# 2.net
KiCad netlist of a schematic drawn in Altium Designer
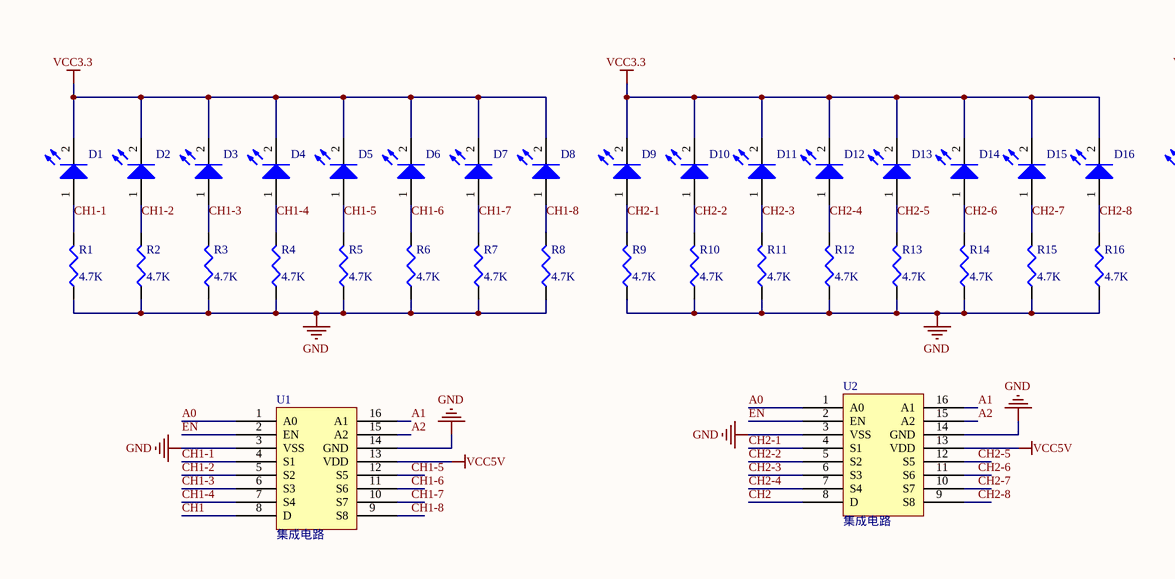
[diagram p0: 数粒机接收板2通道.SchDoc, left]
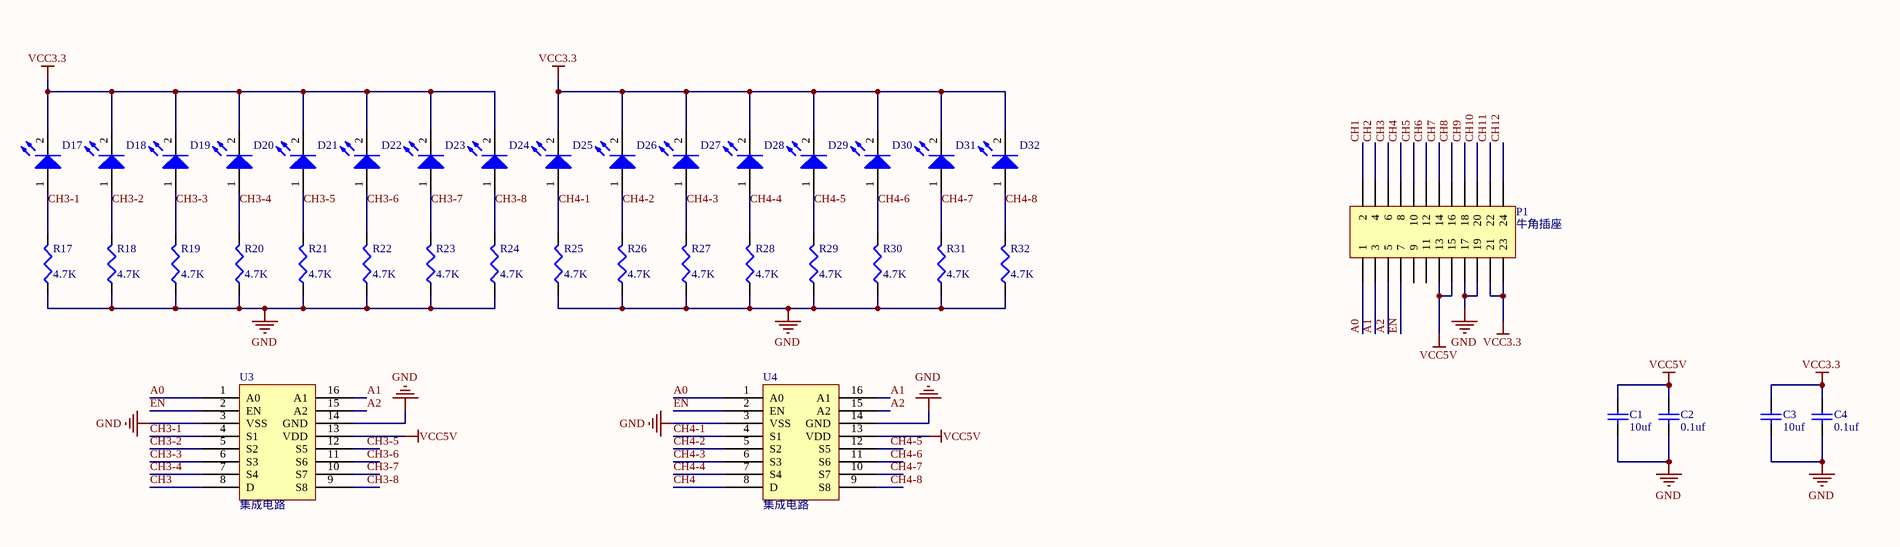
[diagram p1: 数粒机接收板2通道.SchDoc, right]

(export (version "E")
  (design (tool "Eeschema 10.0.6"))
  (components
    (comp (ref "C1")
      (value "10uf")
      (footprint "0805c")
      (description "Capacitor 10uf")
      (fields (field (name "Comment") "贴片电容 10uf") (field (name "PUBLISHER") "Altium Limited"))
      (libsource (lib "Miscellaneous Devices") (part "Cap"))
    )
    (comp (ref "C2")
      (value "0.1uf")
      (footprint "0805c")
      (description "Capacitor 0.1uf")
      (fields (field (name "Comment") "贴片电容 0.1uf") (field (name "PUBLISHER") "Altium Limited"))
      (libsource (lib "Miscellaneous Devices") (part "Cap"))
    )
    (comp (ref "C3")
      (value "10uf")
      (footprint "0805c")
      (description "Capacitor 10uf")
      (fields (field (name "Comment") "贴片电容 10uf") (field (name "PUBLISHER") "Altium Limited"))
      (libsource (lib "Miscellaneous Devices") (part "Cap"))
    )
    (comp (ref "C4")
      (value "0.1uf")
      (footprint "0805c")
      (description "Capacitor 0.1uf")
      (fields (field (name "Comment") "贴片电容 0.1uf") (field (name "PUBLISHER") "Altium Limited"))
      (libsource (lib "Miscellaneous Devices") (part "Cap"))
    )
    (comp (ref "D1")
      (value "红外接收珠子")
      (footprint "jieshou1206")
      (description "PD15-21B/TR8")
      (fields (field (name "PUBLISHER") "Altium Limited"))
      (libsource (lib "Miscellaneous Devices") (part "PD15-21B/TR8"))
    )
    (comp (ref "D2")
      (value "红外接收珠子")
      (footprint "jieshou1206")
      (description "PD15-21B/TR8")
      (fields (field (name "PUBLISHER") "Altium Limited"))
      (libsource (lib "Miscellaneous Devices") (part "PD15-21B/TR8"))
    )
    (comp (ref "D3")
      (value "红外接收珠子")
      (footprint "jieshou1206")
      (description "PD15-21B/TR8")
      (fields (field (name "PUBLISHER") "Altium Limited"))
      (libsource (lib "Miscellaneous Devices") (part "PD15-21B/TR8"))
    )
    (comp (ref "D4")
      (value "红外接收珠子")
      (footprint "jieshou1206")
      (description "PD15-21B/TR8")
      (fields (field (name "PUBLISHER") "Altium Limited"))
      (libsource (lib "Miscellaneous Devices") (part "PD15-21B/TR8"))
    )
    (comp (ref "D5")
      (value "红外接收珠子")
      (footprint "jieshou1206")
      (description "PD15-21B/TR8")
      (fields (field (name "PUBLISHER") "Altium Limited"))
      (libsource (lib "Miscellaneous Devices") (part "PD15-21B/TR8"))
    )
    (comp (ref "D6")
      (value "红外接收珠子")
      (footprint "jieshou1206")
      (description "PD15-21B/TR8")
      (fields (field (name "PUBLISHER") "Altium Limited"))
      (libsource (lib "Miscellaneous Devices") (part "PD15-21B/TR8"))
    )
    (comp (ref "D7")
      (value "红外接收珠子")
      (footprint "jieshou1206")
      (description "PD15-21B/TR8")
      (fields (field (name "PUBLISHER") "Altium Limited"))
      (libsource (lib "Miscellaneous Devices") (part "PD15-21B/TR8"))
    )
    (comp (ref "D8")
      (value "红外接收珠子")
      (footprint "jieshou1206")
      (description "PD15-21B/TR8")
      (fields (field (name "PUBLISHER") "Altium Limited"))
      (libsource (lib "Miscellaneous Devices") (part "PD15-21B/TR8"))
    )
    (comp (ref "D9")
      (value "红外接收珠子")
      (footprint "jieshou1206")
      (description "PD15-21B/TR8")
      (fields (field (name "PUBLISHER") "Altium Limited"))
      (libsource (lib "Miscellaneous Devices") (part "PD15-21B/TR8"))
    )
    (comp (ref "D10")
      (value "红外接收珠子")
      (footprint "jieshou1206")
      (description "PD15-21B/TR8")
      (fields (field (name "PUBLISHER") "Altium Limited"))
      (libsource (lib "Miscellaneous Devices") (part "PD15-21B/TR8"))
    )
    (comp (ref "D11")
      (value "红外接收珠子")
      (footprint "jieshou1206")
      (description "PD15-21B/TR8")
      (fields (field (name "PUBLISHER") "Altium Limited"))
      (libsource (lib "Miscellaneous Devices") (part "PD15-21B/TR8"))
    )
    (comp (ref "D12")
      (value "红外接收珠子")
      (footprint "jieshou1206")
      (description "PD15-21B/TR8")
      (fields (field (name "PUBLISHER") "Altium Limited"))
      (libsource (lib "Miscellaneous Devices") (part "PD15-21B/TR8"))
    )
    (comp (ref "D13")
      (value "红外接收珠子")
      (footprint "jieshou1206")
      (description "PD15-21B/TR8")
      (fields (field (name "PUBLISHER") "Altium Limited"))
      (libsource (lib "Miscellaneous Devices") (part "PD15-21B/TR8"))
    )
    (comp (ref "D14")
      (value "红外接收珠子")
      (footprint "jieshou1206")
      (description "PD15-21B/TR8")
      (fields (field (name "PUBLISHER") "Altium Limited"))
      (libsource (lib "Miscellaneous Devices") (part "PD15-21B/TR8"))
    )
    (comp (ref "D15")
      (value "红外接收珠子")
      (footprint "jieshou1206")
      (description "PD15-21B/TR8")
      (fields (field (name "PUBLISHER") "Altium Limited"))
      (libsource (lib "Miscellaneous Devices") (part "PD15-21B/TR8"))
    )
    (comp (ref "D16")
      (value "红外接收珠子")
      (footprint "jieshou1206")
      (description "PD15-21B/TR8")
      (fields (field (name "PUBLISHER") "Altium Limited"))
      (libsource (lib "Miscellaneous Devices") (part "PD15-21B/TR8"))
    )
    (comp (ref "D17")
      (value "红外接收珠子")
      (footprint "jieshou1206")
      (description "PD15-21B/TR8")
      (fields (field (name "PUBLISHER") "Altium Limited"))
      (libsource (lib "Miscellaneous Devices") (part "PD15-21B/TR8"))
    )
    (comp (ref "D18")
      (value "红外接收珠子")
      (footprint "jieshou1206")
      (description "PD15-21B/TR8")
      (fields (field (name "PUBLISHER") "Altium Limited"))
      (libsource (lib "Miscellaneous Devices") (part "PD15-21B/TR8"))
    )
    (comp (ref "D19")
      (value "红外接收珠子")
      (footprint "jieshou1206")
      (description "PD15-21B/TR8")
      (fields (field (name "PUBLISHER") "Altium Limited"))
      (libsource (lib "Miscellaneous Devices") (part "PD15-21B/TR8"))
    )
    (comp (ref "D20")
      (value "红外接收珠子")
      (footprint "jieshou1206")
      (description "PD15-21B/TR8")
      (fields (field (name "PUBLISHER") "Altium Limited"))
      (libsource (lib "Miscellaneous Devices") (part "PD15-21B/TR8"))
    )
    (comp (ref "D21")
      (value "红外接收珠子")
      (footprint "jieshou1206")
      (description "PD15-21B/TR8")
      (fields (field (name "PUBLISHER") "Altium Limited"))
      (libsource (lib "Miscellaneous Devices") (part "PD15-21B/TR8"))
    )
    (comp (ref "D22")
      (value "红外接收珠子")
      (footprint "jieshou1206")
      (description "PD15-21B/TR8")
      (fields (field (name "PUBLISHER") "Altium Limited"))
      (libsource (lib "Miscellaneous Devices") (part "PD15-21B/TR8"))
    )
    (comp (ref "D23")
      (value "红外接收珠子")
      (footprint "jieshou1206")
      (description "PD15-21B/TR8")
      (fields (field (name "PUBLISHER") "Altium Limited"))
      (libsource (lib "Miscellaneous Devices") (part "PD15-21B/TR8"))
    )
    (comp (ref "D24")
      (value "红外接收珠子")
      (footprint "jieshou1206")
      (description "PD15-21B/TR8")
      (fields (field (name "PUBLISHER") "Altium Limited"))
      (libsource (lib "Miscellaneous Devices") (part "PD15-21B/TR8"))
    )
    (comp (ref "D25")
      (value "红外接收珠子")
      (footprint "jieshou1206")
      (description "PD15-21B/TR8")
      (fields (field (name "PUBLISHER") "Altium Limited"))
      (libsource (lib "Miscellaneous Devices") (part "PD15-21B/TR8"))
    )
    (comp (ref "D26")
      (value "红外接收珠子")
      (footprint "jieshou1206")
      (description "PD15-21B/TR8")
      (fields (field (name "PUBLISHER") "Altium Limited"))
      (libsource (lib "Miscellaneous Devices") (part "PD15-21B/TR8"))
    )
    (comp (ref "D27")
      (value "红外接收珠子")
      (footprint "jieshou1206")
      (description "PD15-21B/TR8")
      (fields (field (name "PUBLISHER") "Altium Limited"))
      (libsource (lib "Miscellaneous Devices") (part "PD15-21B/TR8"))
    )
    (comp (ref "D28")
      (value "红外接收珠子")
      (footprint "jieshou1206")
      (description "PD15-21B/TR8")
      (fields (field (name "PUBLISHER") "Altium Limited"))
      (libsource (lib "Miscellaneous Devices") (part "PD15-21B/TR8"))
    )
    (comp (ref "D29")
      (value "红外接收珠子")
      (footprint "jieshou1206")
      (description "PD15-21B/TR8")
      (fields (field (name "PUBLISHER") "Altium Limited"))
      (libsource (lib "Miscellaneous Devices") (part "PD15-21B/TR8"))
    )
    (comp (ref "D30")
      (value "红外接收珠子")
      (footprint "jieshou1206")
      (description "PD15-21B/TR8")
      (fields (field (name "PUBLISHER") "Altium Limited"))
      (libsource (lib "Miscellaneous Devices") (part "PD15-21B/TR8"))
    )
    (comp (ref "D31")
      (value "红外接收珠子")
      (footprint "jieshou1206")
      (description "PD15-21B/TR8")
      (fields (field (name "PUBLISHER") "Altium Limited"))
      (libsource (lib "Miscellaneous Devices") (part "PD15-21B/TR8"))
    )
    (comp (ref "D32")
      (value "红外接收珠子")
      (footprint "jieshou1206")
      (description "PD15-21B/TR8")
      (fields (field (name "PUBLISHER") "Altium Limited"))
      (libsource (lib "Miscellaneous Devices") (part "PD15-21B/TR8"))
    )
    (comp (ref "P1")
      (value "牛角插座")
      (footprint "HDR2X12")
      (description "Header, 12-Pin, Dual row")
      (fields (field (name "PUBLISHER") "Altium Limited"))
      (libsource (lib "Miscellaneous Connectors") (part "Header 12X2"))
    )
    (comp (ref "R1")
      (value "4.7K")
      (footprint "0805r")
      (description "电阻")
      (fields (field (name "Comment") "贴片电阻") (field (name "PUBLISHER") "Altium Limited"))
      (libsource (lib "Miscellaneous Devices") (part "Res3"))
    )
    (comp (ref "R2")
      (value "4.7K")
      (footprint "0805r")
      (description "电阻")
      (fields (field (name "Comment") "贴片电阻") (field (name "PUBLISHER") "Altium Limited"))
      (libsource (lib "Miscellaneous Devices") (part "Res3"))
    )
    (comp (ref "R3")
      (value "4.7K")
      (footprint "0805r")
      (description "电阻")
      (fields (field (name "Comment") "贴片电阻") (field (name "PUBLISHER") "Altium Limited"))
      (libsource (lib "Miscellaneous Devices") (part "Res3"))
    )
    (comp (ref "R4")
      (value "4.7K")
      (footprint "0805r")
      (description "电阻")
      (fields (field (name "Comment") "贴片电阻") (field (name "PUBLISHER") "Altium Limited"))
      (libsource (lib "Miscellaneous Devices") (part "Res3"))
    )
    (comp (ref "R5")
      (value "4.7K")
      (footprint "0805r")
      (description "电阻")
      (fields (field (name "Comment") "贴片电阻") (field (name "PUBLISHER") "Altium Limited"))
      (libsource (lib "Miscellaneous Devices") (part "Res3"))
    )
    (comp (ref "R6")
      (value "4.7K")
      (footprint "0805r")
      (description "电阻")
      (fields (field (name "Comment") "贴片电阻") (field (name "PUBLISHER") "Altium Limited"))
      (libsource (lib "Miscellaneous Devices") (part "Res3"))
    )
    (comp (ref "R7")
      (value "4.7K")
      (footprint "0805r")
      (description "电阻")
      (fields (field (name "Comment") "贴片电阻") (field (name "PUBLISHER") "Altium Limited"))
      (libsource (lib "Miscellaneous Devices") (part "Res3"))
    )
    (comp (ref "R8")
      (value "4.7K")
      (footprint "0805r")
      (description "电阻")
      (fields (field (name "Comment") "贴片电阻") (field (name "PUBLISHER") "Altium Limited"))
      (libsource (lib "Miscellaneous Devices") (part "Res3"))
    )
    (comp (ref "R9")
      (value "4.7K")
      (footprint "0805r")
      (description "电阻")
      (fields (field (name "Comment") "贴片电阻") (field (name "PUBLISHER") "Altium Limited"))
      (libsource (lib "Miscellaneous Devices") (part "Res3"))
    )
    (comp (ref "R10")
      (value "4.7K")
      (footprint "0805r")
      (description "电阻")
      (fields (field (name "Comment") "贴片电阻") (field (name "PUBLISHER") "Altium Limited"))
      (libsource (lib "Miscellaneous Devices") (part "Res3"))
    )
    (comp (ref "R11")
      (value "4.7K")
      (footprint "0805r")
      (description "电阻")
      (fields (field (name "Comment") "贴片电阻") (field (name "PUBLISHER") "Altium Limited"))
      (libsource (lib "Miscellaneous Devices") (part "Res3"))
    )
    (comp (ref "R12")
      (value "4.7K")
      (footprint "0805r")
      (description "电阻")
      (fields (field (name "Comment") "贴片电阻") (field (name "PUBLISHER") "Altium Limited"))
      (libsource (lib "Miscellaneous Devices") (part "Res3"))
    )
    (comp (ref "R13")
      (value "4.7K")
      (footprint "0805r")
      (description "电阻")
      (fields (field (name "Comment") "贴片电阻") (field (name "PUBLISHER") "Altium Limited"))
      (libsource (lib "Miscellaneous Devices") (part "Res3"))
    )
    (comp (ref "R14")
      (value "4.7K")
      (footprint "0805r")
      (description "电阻")
      (fields (field (name "Comment") "贴片电阻") (field (name "PUBLISHER") "Altium Limited"))
      (libsource (lib "Miscellaneous Devices") (part "Res3"))
    )
    (comp (ref "R15")
      (value "4.7K")
      (footprint "0805r")
      (description "电阻")
      (fields (field (name "Comment") "贴片电阻") (field (name "PUBLISHER") "Altium Limited"))
      (libsource (lib "Miscellaneous Devices") (part "Res3"))
    )
    (comp (ref "R16")
      (value "4.7K")
      (footprint "0805r")
      (description "电阻")
      (fields (field (name "Comment") "贴片电阻") (field (name "PUBLISHER") "Altium Limited"))
      (libsource (lib "Miscellaneous Devices") (part "Res3"))
    )
    (comp (ref "R17")
      (value "4.7K")
      (footprint "0805r")
      (description "电阻")
      (fields (field (name "Comment") "贴片电阻") (field (name "PUBLISHER") "Altium Limited"))
      (libsource (lib "Miscellaneous Devices") (part "Res3"))
    )
    (comp (ref "R18")
      (value "4.7K")
      (footprint "0805r")
      (description "电阻")
      (fields (field (name "Comment") "贴片电阻") (field (name "PUBLISHER") "Altium Limited"))
      (libsource (lib "Miscellaneous Devices") (part "Res3"))
    )
    (comp (ref "R19")
      (value "4.7K")
      (footprint "0805r")
      (description "电阻")
      (fields (field (name "Comment") "贴片电阻") (field (name "PUBLISHER") "Altium Limited"))
      (libsource (lib "Miscellaneous Devices") (part "Res3"))
    )
    (comp (ref "R20")
      (value "4.7K")
      (footprint "0805r")
      (description "电阻")
      (fields (field (name "Comment") "贴片电阻") (field (name "PUBLISHER") "Altium Limited"))
      (libsource (lib "Miscellaneous Devices") (part "Res3"))
    )
    (comp (ref "R21")
      (value "4.7K")
      (footprint "0805r")
      (description "电阻")
      (fields (field (name "Comment") "贴片电阻") (field (name "PUBLISHER") "Altium Limited"))
      (libsource (lib "Miscellaneous Devices") (part "Res3"))
    )
    (comp (ref "R22")
      (value "4.7K")
      (footprint "0805r")
      (description "电阻")
      (fields (field (name "Comment") "贴片电阻") (field (name "PUBLISHER") "Altium Limited"))
      (libsource (lib "Miscellaneous Devices") (part "Res3"))
    )
    (comp (ref "R23")
      (value "4.7K")
      (footprint "0805r")
      (description "电阻")
      (fields (field (name "Comment") "贴片电阻") (field (name "PUBLISHER") "Altium Limited"))
      (libsource (lib "Miscellaneous Devices") (part "Res3"))
    )
    (comp (ref "R24")
      (value "4.7K")
      (footprint "0805r")
      (description "电阻")
      (fields (field (name "Comment") "贴片电阻") (field (name "PUBLISHER") "Altium Limited"))
      (libsource (lib "Miscellaneous Devices") (part "Res3"))
    )
    (comp (ref "R25")
      (value "4.7K")
      (footprint "0805r")
      (description "电阻")
      (fields (field (name "Comment") "贴片电阻") (field (name "PUBLISHER") "Altium Limited"))
      (libsource (lib "Miscellaneous Devices") (part "Res3"))
    )
    (comp (ref "R26")
      (value "4.7K")
      (footprint "0805r")
      (description "电阻")
      (fields (field (name "Comment") "贴片电阻") (field (name "PUBLISHER") "Altium Limited"))
      (libsource (lib "Miscellaneous Devices") (part "Res3"))
    )
    (comp (ref "R27")
      (value "4.7K")
      (footprint "0805r")
      (description "电阻")
      (fields (field (name "Comment") "贴片电阻") (field (name "PUBLISHER") "Altium Limited"))
      (libsource (lib "Miscellaneous Devices") (part "Res3"))
    )
    (comp (ref "R28")
      (value "4.7K")
      (footprint "0805r")
      (description "电阻")
      (fields (field (name "Comment") "贴片电阻") (field (name "PUBLISHER") "Altium Limited"))
      (libsource (lib "Miscellaneous Devices") (part "Res3"))
    )
    (comp (ref "R29")
      (value "4.7K")
      (footprint "0805r")
      (description "电阻")
      (fields (field (name "Comment") "贴片电阻") (field (name "PUBLISHER") "Altium Limited"))
      (libsource (lib "Miscellaneous Devices") (part "Res3"))
    )
    (comp (ref "R30")
      (value "4.7K")
      (footprint "0805r")
      (description "电阻")
      (fields (field (name "Comment") "贴片电阻") (field (name "PUBLISHER") "Altium Limited"))
      (libsource (lib "Miscellaneous Devices") (part "Res3"))
    )
    (comp (ref "R31")
      (value "4.7K")
      (footprint "0805r")
      (description "电阻")
      (fields (field (name "Comment") "贴片电阻") (field (name "PUBLISHER") "Altium Limited"))
      (libsource (lib "Miscellaneous Devices") (part "Res3"))
    )
    (comp (ref "R32")
      (value "4.7K")
      (footprint "0805r")
      (description "电阻")
      (fields (field (name "Comment") "贴片电阻") (field (name "PUBLISHER") "Altium Limited"))
      (libsource (lib "Miscellaneous Devices") (part "Res3"))
    )
    (comp (ref "U1")
      (value "集成电路")
      (footprint "TSSOP16")
      (description "ADG708BRU-REEL")
      (libsource (lib "MYlib") (part "ADG708"))
    )
    (comp (ref "U2")
      (value "集成电路")
      (footprint "TSSOP16")
      (description "ADG708BRU-REEL")
      (libsource (lib "MYlib") (part "ADG708"))
    )
    (comp (ref "U3")
      (value "集成电路")
      (footprint "TSSOP16")
      (description "ADG708BRU-REEL")
      (libsource (lib "MYlib") (part "ADG708"))
    )
    (comp (ref "U4")
      (value "集成电路")
      (footprint "TSSOP16")
      (description "ADG708BRU-REEL")
      (libsource (lib "MYlib") (part "ADG708"))
    )
  )
  (nets
    (net (code "1") (name "/A0") (class "Default")
      (node (ref "P1") (pin "1") (pinfunction "1_1") (pintype "passive"))
      (node (ref "U1") (pin "1") (pinfunction "A0_1") (pintype "passive"))
      (node (ref "U2") (pin "1") (pinfunction "A0_1") (pintype "passive"))
      (node (ref "U3") (pin "1") (pinfunction "A0_1") (pintype "passive"))
      (node (ref "U4") (pin "1") (pinfunction "A0_1") (pintype "passive"))
    )
    (net (code "2") (name "/A1") (class "Default")
      (node (ref "P1") (pin "3") (pinfunction "3_3") (pintype "passive"))
      (node (ref "U1") (pin "16") (pinfunction "A1_16") (pintype "passive"))
      (node (ref "U2") (pin "16") (pinfunction "A1_16") (pintype "passive"))
      (node (ref "U3") (pin "16") (pinfunction "A1_16") (pintype "passive"))
      (node (ref "U4") (pin "16") (pinfunction "A1_16") (pintype "passive"))
    )
    (net (code "3") (name "/A2") (class "Default")
      (node (ref "P1") (pin "5") (pinfunction "5_5") (pintype "passive"))
      (node (ref "U1") (pin "15") (pinfunction "A2_15") (pintype "passive"))
      (node (ref "U2") (pin "15") (pinfunction "A2_15") (pintype "passive"))
      (node (ref "U3") (pin "15") (pinfunction "A2_15") (pintype "passive"))
      (node (ref "U4") (pin "15") (pinfunction "A2_15") (pintype "passive"))
    )
    (net (code "4") (name "/CH1") (class "Default")
      (node (ref "P1") (pin "2") (pinfunction "2_2") (pintype "passive"))
      (node (ref "U1") (pin "8") (pinfunction "D_8") (pintype "passive"))
    )
    (net (code "5") (name "/CH1-1") (class "Default")
      (node (ref "D1") (pin "1") (pinfunction "A_1") (pintype "passive"))
      (node (ref "R1") (pin "2") (pinfunction "2_2") (pintype "passive"))
      (node (ref "U1") (pin "4") (pinfunction "S1_4") (pintype "passive"))
    )
    (net (code "6") (name "/CH1-2") (class "Default")
      (node (ref "D2") (pin "1") (pinfunction "A_1") (pintype "passive"))
      (node (ref "R2") (pin "2") (pinfunction "2_2") (pintype "passive"))
      (node (ref "U1") (pin "5") (pinfunction "S2_5") (pintype "passive"))
    )
    (net (code "7") (name "/CH1-3") (class "Default")
      (node (ref "D3") (pin "1") (pinfunction "A_1") (pintype "passive"))
      (node (ref "R3") (pin "2") (pinfunction "2_2") (pintype "passive"))
      (node (ref "U1") (pin "6") (pinfunction "S3_6") (pintype "passive"))
    )
    (net (code "8") (name "/CH1-4") (class "Default")
      (node (ref "D4") (pin "1") (pinfunction "A_1") (pintype "passive"))
      (node (ref "R4") (pin "2") (pinfunction "2_2") (pintype "passive"))
      (node (ref "U1") (pin "7") (pinfunction "S4_7") (pintype "passive"))
    )
    (net (code "9") (name "/CH1-5") (class "Default")
      (node (ref "D5") (pin "1") (pinfunction "A_1") (pintype "passive"))
      (node (ref "R5") (pin "2") (pinfunction "2_2") (pintype "passive"))
      (node (ref "U1") (pin "12") (pinfunction "S5_12") (pintype "passive"))
    )
    (net (code "10") (name "/CH1-6") (class "Default")
      (node (ref "D6") (pin "1") (pinfunction "A_1") (pintype "passive"))
      (node (ref "R6") (pin "2") (pinfunction "2_2") (pintype "passive"))
      (node (ref "U1") (pin "11") (pinfunction "S6_11") (pintype "passive"))
    )
    (net (code "11") (name "/CH1-7") (class "Default")
      (node (ref "D7") (pin "1") (pinfunction "A_1") (pintype "passive"))
      (node (ref "R7") (pin "2") (pinfunction "2_2") (pintype "passive"))
      (node (ref "U1") (pin "10") (pinfunction "S7_10") (pintype "passive"))
    )
    (net (code "12") (name "/CH1-8") (class "Default")
      (node (ref "D8") (pin "1") (pinfunction "A_1") (pintype "passive"))
      (node (ref "R8") (pin "2") (pinfunction "2_2") (pintype "passive"))
      (node (ref "U1") (pin "9") (pinfunction "S8_9") (pintype "passive"))
    )
    (net (code "13") (name "/CH2") (class "Default")
      (node (ref "P1") (pin "4") (pinfunction "4_4") (pintype "passive"))
      (node (ref "U2") (pin "8") (pinfunction "D_8") (pintype "passive"))
    )
    (net (code "14") (name "/CH2-1") (class "Default")
      (node (ref "D9") (pin "1") (pinfunction "A_1") (pintype "passive"))
      (node (ref "R9") (pin "2") (pinfunction "2_2") (pintype "passive"))
      (node (ref "U2") (pin "4") (pinfunction "S1_4") (pintype "passive"))
    )
    (net (code "15") (name "/CH2-2") (class "Default")
      (node (ref "D10") (pin "1") (pinfunction "A_1") (pintype "passive"))
      (node (ref "R10") (pin "2") (pinfunction "2_2") (pintype "passive"))
      (node (ref "U2") (pin "5") (pinfunction "S2_5") (pintype "passive"))
    )
    (net (code "16") (name "/CH2-3") (class "Default")
      (node (ref "D11") (pin "1") (pinfunction "A_1") (pintype "passive"))
      (node (ref "R11") (pin "2") (pinfunction "2_2") (pintype "passive"))
      (node (ref "U2") (pin "6") (pinfunction "S3_6") (pintype "passive"))
    )
    (net (code "17") (name "/CH2-4") (class "Default")
      (node (ref "D12") (pin "1") (pinfunction "A_1") (pintype "passive"))
      (node (ref "R12") (pin "2") (pinfunction "2_2") (pintype "passive"))
      (node (ref "U2") (pin "7") (pinfunction "S4_7") (pintype "passive"))
    )
    (net (code "18") (name "/CH2-5") (class "Default")
      (node (ref "D13") (pin "1") (pinfunction "A_1") (pintype "passive"))
      (node (ref "R13") (pin "2") (pinfunction "2_2") (pintype "passive"))
      (node (ref "U2") (pin "12") (pinfunction "S5_12") (pintype "passive"))
    )
    (net (code "19") (name "/CH2-6") (class "Default")
      (node (ref "D14") (pin "1") (pinfunction "A_1") (pintype "passive"))
      (node (ref "R14") (pin "2") (pinfunction "2_2") (pintype "passive"))
      (node (ref "U2") (pin "11") (pinfunction "S6_11") (pintype "passive"))
    )
    (net (code "20") (name "/CH2-7") (class "Default")
      (node (ref "D15") (pin "1") (pinfunction "A_1") (pintype "passive"))
      (node (ref "R15") (pin "2") (pinfunction "2_2") (pintype "passive"))
      (node (ref "U2") (pin "10") (pinfunction "S7_10") (pintype "passive"))
    )
    (net (code "21") (name "/CH2-8") (class "Default")
      (node (ref "D16") (pin "1") (pinfunction "A_1") (pintype "passive"))
      (node (ref "R16") (pin "2") (pinfunction "2_2") (pintype "passive"))
      (node (ref "U2") (pin "9") (pinfunction "S8_9") (pintype "passive"))
    )
    (net (code "22") (name "/CH3") (class "Default")
      (node (ref "P1") (pin "6") (pinfunction "6_6") (pintype "passive"))
      (node (ref "U3") (pin "8") (pinfunction "D_8") (pintype "passive"))
    )
    (net (code "23") (name "/CH3-1") (class "Default")
      (node (ref "D17") (pin "1") (pinfunction "A_1") (pintype "passive"))
      (node (ref "R17") (pin "2") (pinfunction "2_2") (pintype "passive"))
      (node (ref "U3") (pin "4") (pinfunction "S1_4") (pintype "passive"))
    )
    (net (code "24") (name "/CH3-2") (class "Default")
      (node (ref "D18") (pin "1") (pinfunction "A_1") (pintype "passive"))
      (node (ref "R18") (pin "2") (pinfunction "2_2") (pintype "passive"))
      (node (ref "U3") (pin "5") (pinfunction "S2_5") (pintype "passive"))
    )
    (net (code "25") (name "/CH3-3") (class "Default")
      (node (ref "D19") (pin "1") (pinfunction "A_1") (pintype "passive"))
      (node (ref "R19") (pin "2") (pinfunction "2_2") (pintype "passive"))
      (node (ref "U3") (pin "6") (pinfunction "S3_6") (pintype "passive"))
    )
    (net (code "26") (name "/CH3-4") (class "Default")
      (node (ref "D20") (pin "1") (pinfunction "A_1") (pintype "passive"))
      (node (ref "R20") (pin "2") (pinfunction "2_2") (pintype "passive"))
      (node (ref "U3") (pin "7") (pinfunction "S4_7") (pintype "passive"))
    )
    (net (code "27") (name "/CH3-5") (class "Default")
      (node (ref "D21") (pin "1") (pinfunction "A_1") (pintype "passive"))
      (node (ref "R21") (pin "2") (pinfunction "2_2") (pintype "passive"))
      (node (ref "U3") (pin "12") (pinfunction "S5_12") (pintype "passive"))
    )
    (net (code "28") (name "/CH3-6") (class "Default")
      (node (ref "D22") (pin "1") (pinfunction "A_1") (pintype "passive"))
      (node (ref "R22") (pin "2") (pinfunction "2_2") (pintype "passive"))
      (node (ref "U3") (pin "11") (pinfunction "S6_11") (pintype "passive"))
    )
    (net (code "29") (name "/CH3-7") (class "Default")
      (node (ref "D23") (pin "1") (pinfunction "A_1") (pintype "passive"))
      (node (ref "R23") (pin "2") (pinfunction "2_2") (pintype "passive"))
      (node (ref "U3") (pin "10") (pinfunction "S7_10") (pintype "passive"))
    )
    (net (code "30") (name "/CH3-8") (class "Default")
      (node (ref "D24") (pin "1") (pinfunction "A_1") (pintype "passive"))
      (node (ref "R24") (pin "2") (pinfunction "2_2") (pintype "passive"))
      (node (ref "U3") (pin "9") (pinfunction "S8_9") (pintype "passive"))
    )
    (net (code "31") (name "/CH4") (class "Default")
      (node (ref "P1") (pin "8") (pinfunction "8_8") (pintype "passive"))
      (node (ref "U4") (pin "8") (pinfunction "D_8") (pintype "passive"))
    )
    (net (code "32") (name "/CH4-1") (class "Default")
      (node (ref "D25") (pin "1") (pinfunction "A_1") (pintype "passive"))
      (node (ref "R25") (pin "2") (pinfunction "2_2") (pintype "passive"))
      (node (ref "U4") (pin "4") (pinfunction "S1_4") (pintype "passive"))
    )
    (net (code "33") (name "/CH4-2") (class "Default")
      (node (ref "D26") (pin "1") (pinfunction "A_1") (pintype "passive"))
      (node (ref "R26") (pin "2") (pinfunction "2_2") (pintype "passive"))
      (node (ref "U4") (pin "5") (pinfunction "S2_5") (pintype "passive"))
    )
    (net (code "34") (name "/CH4-3") (class "Default")
      (node (ref "D27") (pin "1") (pinfunction "A_1") (pintype "passive"))
      (node (ref "R27") (pin "2") (pinfunction "2_2") (pintype "passive"))
      (node (ref "U4") (pin "6") (pinfunction "S3_6") (pintype "passive"))
    )
    (net (code "35") (name "/CH4-4") (class "Default")
      (node (ref "D28") (pin "1") (pinfunction "A_1") (pintype "passive"))
      (node (ref "R28") (pin "2") (pinfunction "2_2") (pintype "passive"))
      (node (ref "U4") (pin "7") (pinfunction "S4_7") (pintype "passive"))
    )
    (net (code "36") (name "/CH4-5") (class "Default")
      (node (ref "D29") (pin "1") (pinfunction "A_1") (pintype "passive"))
      (node (ref "R29") (pin "2") (pinfunction "2_2") (pintype "passive"))
      (node (ref "U4") (pin "12") (pinfunction "S5_12") (pintype "passive"))
    )
    (net (code "37") (name "/CH4-6") (class "Default")
      (node (ref "D30") (pin "1") (pinfunction "A_1") (pintype "passive"))
      (node (ref "R30") (pin "2") (pinfunction "2_2") (pintype "passive"))
      (node (ref "U4") (pin "11") (pinfunction "S6_11") (pintype "passive"))
    )
    (net (code "38") (name "/CH4-7") (class "Default")
      (node (ref "D31") (pin "1") (pinfunction "A_1") (pintype "passive"))
      (node (ref "R31") (pin "2") (pinfunction "2_2") (pintype "passive"))
      (node (ref "U4") (pin "10") (pinfunction "S7_10") (pintype "passive"))
    )
    (net (code "39") (name "/CH4-8") (class "Default")
      (node (ref "D32") (pin "1") (pinfunction "A_1") (pintype "passive"))
      (node (ref "R32") (pin "2") (pinfunction "2_2") (pintype "passive"))
      (node (ref "U4") (pin "9") (pinfunction "S8_9") (pintype "passive"))
    )
    (net (code "40") (name "/CH5") (class "Default")
      (node (ref "P1") (pin "10") (pinfunction "10_10") (pintype "passive"))
    )
    (net (code "41") (name "/CH6") (class "Default")
      (node (ref "P1") (pin "12") (pinfunction "12_12") (pintype "passive"))
    )
    (net (code "42") (name "/CH7") (class "Default")
      (node (ref "P1") (pin "14") (pinfunction "14_14") (pintype "passive"))
    )
    (net (code "43") (name "/CH8") (class "Default")
      (node (ref "P1") (pin "16") (pinfunction "16_16") (pintype "passive"))
    )
    (net (code "44") (name "/CH9") (class "Default")
      (node (ref "P1") (pin "18") (pinfunction "18_18") (pintype "passive"))
    )
    (net (code "45") (name "/CH10") (class "Default")
      (node (ref "P1") (pin "20") (pinfunction "20_20") (pintype "passive"))
    )
    (net (code "46") (name "/CH11") (class "Default")
      (node (ref "P1") (pin "22") (pinfunction "22_22") (pintype "passive"))
    )
    (net (code "47") (name "/CH12") (class "Default")
      (node (ref "P1") (pin "24") (pinfunction "24_24") (pintype "passive"))
    )
    (net (code "48") (name "/EN") (class "Default")
      (node (ref "P1") (pin "7") (pinfunction "7_7") (pintype "passive"))
      (node (ref "U1") (pin "2") (pinfunction "EN_2") (pintype "passive"))
      (node (ref "U2") (pin "2") (pinfunction "EN_2") (pintype "passive"))
      (node (ref "U3") (pin "2") (pinfunction "EN_2") (pintype "passive"))
      (node (ref "U4") (pin "2") (pinfunction "EN_2") (pintype "passive"))
    )
    (net (code "49") (name "GND") (class "Default")
      (node (ref "C1") (pin "1") (pinfunction "1_1") (pintype "passive"))
      (node (ref "C2") (pin "1") (pinfunction "1_1") (pintype "passive"))
      (node (ref "C3") (pin "1") (pinfunction "1_1") (pintype "passive"))
      (node (ref "C4") (pin "1") (pinfunction "1_1") (pintype "passive"))
      (node (ref "P1") (pin "17") (pinfunction "17_17") (pintype "passive"))
      (node (ref "P1") (pin "19") (pinfunction "19_19") (pintype "passive"))
      (node (ref "R1") (pin "1") (pinfunction "1_1") (pintype "passive"))
      (node (ref "R10") (pin "1") (pinfunction "1_1") (pintype "passive"))
      (node (ref "R11") (pin "1") (pinfunction "1_1") (pintype "passive"))
      (node (ref "R12") (pin "1") (pinfunction "1_1") (pintype "passive"))
      (node (ref "R13") (pin "1") (pinfunction "1_1") (pintype "passive"))
      (node (ref "R14") (pin "1") (pinfunction "1_1") (pintype "passive"))
      (node (ref "R15") (pin "1") (pinfunction "1_1") (pintype "passive"))
      (node (ref "R16") (pin "1") (pinfunction "1_1") (pintype "passive"))
      (node (ref "R17") (pin "1") (pinfunction "1_1") (pintype "passive"))
      (node (ref "R18") (pin "1") (pinfunction "1_1") (pintype "passive"))
      (node (ref "R19") (pin "1") (pinfunction "1_1") (pintype "passive"))
      (node (ref "R2") (pin "1") (pinfunction "1_1") (pintype "passive"))
      (node (ref "R20") (pin "1") (pinfunction "1_1") (pintype "passive"))
      (node (ref "R21") (pin "1") (pinfunction "1_1") (pintype "passive"))
      (node (ref "R22") (pin "1") (pinfunction "1_1") (pintype "passive"))
      (node (ref "R23") (pin "1") (pinfunction "1_1") (pintype "passive"))
      (node (ref "R24") (pin "1") (pinfunction "1_1") (pintype "passive"))
      (node (ref "R25") (pin "1") (pinfunction "1_1") (pintype "passive"))
      (node (ref "R26") (pin "1") (pinfunction "1_1") (pintype "passive"))
      (node (ref "R27") (pin "1") (pinfunction "1_1") (pintype "passive"))
      (node (ref "R28") (pin "1") (pinfunction "1_1") (pintype "passive"))
      (node (ref "R29") (pin "1") (pinfunction "1_1") (pintype "passive"))
      (node (ref "R3") (pin "1") (pinfunction "1_1") (pintype "passive"))
      (node (ref "R30") (pin "1") (pinfunction "1_1") (pintype "passive"))
      (node (ref "R31") (pin "1") (pinfunction "1_1") (pintype "passive"))
      (node (ref "R32") (pin "1") (pinfunction "1_1") (pintype "passive"))
      (node (ref "R4") (pin "1") (pinfunction "1_1") (pintype "passive"))
      (node (ref "R5") (pin "1") (pinfunction "1_1") (pintype "passive"))
      (node (ref "R6") (pin "1") (pinfunction "1_1") (pintype "passive"))
      (node (ref "R7") (pin "1") (pinfunction "1_1") (pintype "passive"))
      (node (ref "R8") (pin "1") (pinfunction "1_1") (pintype "passive"))
      (node (ref "R9") (pin "1") (pinfunction "1_1") (pintype "passive"))
      (node (ref "U1") (pin "14") (pinfunction "GND_14") (pintype "passive"))
      (node (ref "U1") (pin "3") (pinfunction "VSS_3") (pintype "passive"))
      (node (ref "U2") (pin "14") (pinfunction "GND_14") (pintype "passive"))
      (node (ref "U2") (pin "3") (pinfunction "VSS_3") (pintype "passive"))
      (node (ref "U3") (pin "14") (pinfunction "GND_14") (pintype "passive"))
      (node (ref "U3") (pin "3") (pinfunction "VSS_3") (pintype "passive"))
      (node (ref "U4") (pin "14") (pinfunction "GND_14") (pintype "passive"))
      (node (ref "U4") (pin "3") (pinfunction "VSS_3") (pintype "passive"))
    )
    (net (code "50") (name "VCC3.3") (class "Default")
      (node (ref "C3") (pin "2") (pinfunction "2_2") (pintype "passive"))
      (node (ref "C4") (pin "2") (pinfunction "2_2") (pintype "passive"))
      (node (ref "D1") (pin "2") (pinfunction "K_2") (pintype "passive"))
      (node (ref "D10") (pin "2") (pinfunction "K_2") (pintype "passive"))
      (node (ref "D11") (pin "2") (pinfunction "K_2") (pintype "passive"))
      (node (ref "D12") (pin "2") (pinfunction "K_2") (pintype "passive"))
      (node (ref "D13") (pin "2") (pinfunction "K_2") (pintype "passive"))
      (node (ref "D14") (pin "2") (pinfunction "K_2") (pintype "passive"))
      (node (ref "D15") (pin "2") (pinfunction "K_2") (pintype "passive"))
      (node (ref "D16") (pin "2") (pinfunction "K_2") (pintype "passive"))
      (node (ref "D17") (pin "2") (pinfunction "K_2") (pintype "passive"))
      (node (ref "D18") (pin "2") (pinfunction "K_2") (pintype "passive"))
      (node (ref "D19") (pin "2") (pinfunction "K_2") (pintype "passive"))
      (node (ref "D2") (pin "2") (pinfunction "K_2") (pintype "passive"))
      (node (ref "D20") (pin "2") (pinfunction "K_2") (pintype "passive"))
      (node (ref "D21") (pin "2") (pinfunction "K_2") (pintype "passive"))
      (node (ref "D22") (pin "2") (pinfunction "K_2") (pintype "passive"))
      (node (ref "D23") (pin "2") (pinfunction "K_2") (pintype "passive"))
      (node (ref "D24") (pin "2") (pinfunction "K_2") (pintype "passive"))
      (node (ref "D25") (pin "2") (pinfunction "K_2") (pintype "passive"))
      (node (ref "D26") (pin "2") (pinfunction "K_2") (pintype "passive"))
      (node (ref "D27") (pin "2") (pinfunction "K_2") (pintype "passive"))
      (node (ref "D28") (pin "2") (pinfunction "K_2") (pintype "passive"))
      (node (ref "D29") (pin "2") (pinfunction "K_2") (pintype "passive"))
      (node (ref "D3") (pin "2") (pinfunction "K_2") (pintype "passive"))
      (node (ref "D30") (pin "2") (pinfunction "K_2") (pintype "passive"))
      (node (ref "D31") (pin "2") (pinfunction "K_2") (pintype "passive"))
      (node (ref "D32") (pin "2") (pinfunction "K_2") (pintype "passive"))
      (node (ref "D4") (pin "2") (pinfunction "K_2") (pintype "passive"))
      (node (ref "D5") (pin "2") (pinfunction "K_2") (pintype "passive"))
      (node (ref "D6") (pin "2") (pinfunction "K_2") (pintype "passive"))
      (node (ref "D7") (pin "2") (pinfunction "K_2") (pintype "passive"))
      (node (ref "D8") (pin "2") (pinfunction "K_2") (pintype "passive"))
      (node (ref "D9") (pin "2") (pinfunction "K_2") (pintype "passive"))
      (node (ref "P1") (pin "21") (pinfunction "21_21") (pintype "passive"))
      (node (ref "P1") (pin "23") (pinfunction "23_23") (pintype "passive"))
    )
    (net (code "51") (name "VCC5V") (class "Default")
      (node (ref "C1") (pin "2") (pinfunction "2_2") (pintype "passive"))
      (node (ref "C2") (pin "2") (pinfunction "2_2") (pintype "passive"))
      (node (ref "P1") (pin "13") (pinfunction "13_13") (pintype "passive"))
      (node (ref "P1") (pin "15") (pinfunction "15_15") (pintype "passive"))
      (node (ref "U1") (pin "13") (pinfunction "VDD_13") (pintype "passive"))
      (node (ref "U2") (pin "13") (pinfunction "VDD_13") (pintype "passive"))
      (node (ref "U3") (pin "13") (pinfunction "VDD_13") (pintype "passive"))
      (node (ref "U4") (pin "13") (pinfunction "VDD_13") (pintype "passive"))
    )
    (net (code "52") (name "unconnected-(P1-Pad9)") (class "Default")
      (node (ref "P1") (pin "9") (pinfunction "9_9") (pintype "passive"))
    )
    (net (code "53") (name "unconnected-(P1-Pad11)") (class "Default")
      (node (ref "P1") (pin "11") (pinfunction "11_11") (pintype "passive"))
    )
  )
)
